# Step-down_converter.net
KiCad netlist of a schematic drawn in Altium Designer
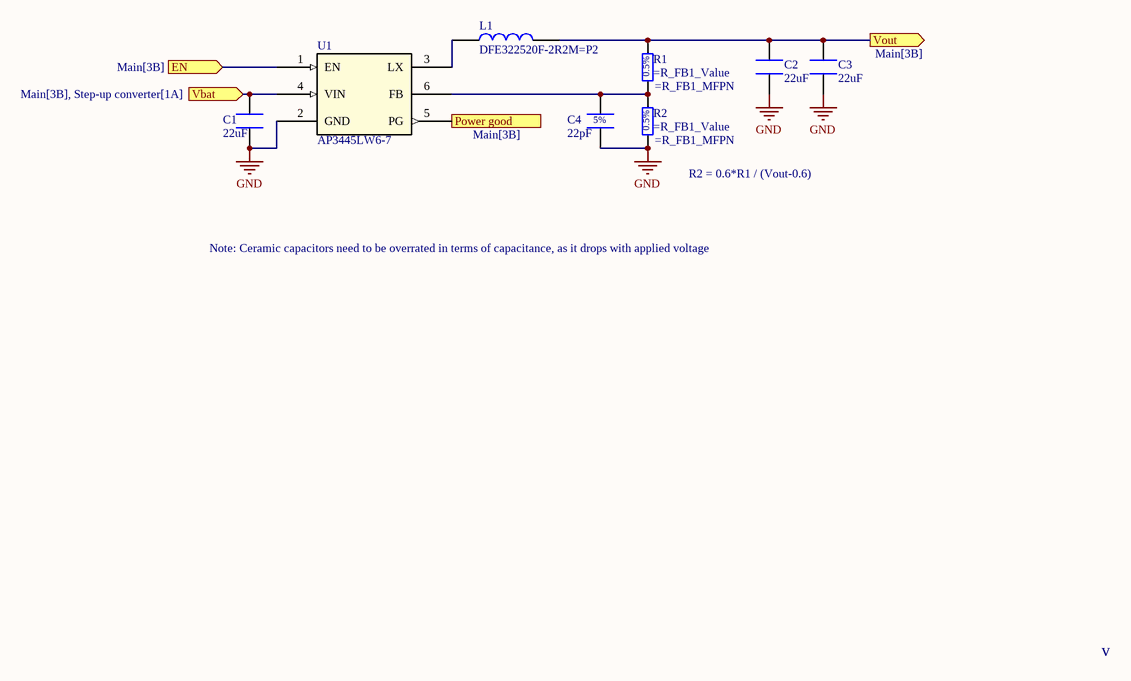
[diagram p0: Step-down converter.SchDoc]

(export (version "E")
  (design (tool "Eeschema 10.0.6"))
  (components
    (comp (ref "C1")
      (value "22uF")
      (footprint "APSS Prototype Parts:CAPACITOR_0805_2012M-70N")
      (description "Passive - Capacitor, X5R, 22uF Max, 6.3V, 0805 (2012 Metric), ±20%, -55°C ~ 85°C. 8.8uF @ 5V")
      (fields (field (name "TOLERANCE") "±20%") (field (name "MF PART NO.") "C0805C226M9PACTU"))
      (libsource (lib "APSS Prototype Parts") (part "C0805C226M9PACTU"))
    )
    (comp (ref "C2")
      (value "22uF")
      (footprint "APSS Prototype Parts:CAPACITOR_0805_2012M-70N")
      (description "Passive - Capacitor, X5R, 22uF Max, 6.3V, 0805 (2012 Metric), ±20%, -55°C ~ 85°C. 8.8uF @ 5V")
      (fields (field (name "TOLERANCE") "±20%") (field (name "MF PART NO.") "C0805C226M9PACTU"))
      (libsource (lib "APSS Prototype Parts") (part "C0805C226M9PACTU"))
    )
    (comp (ref "C3")
      (value "22uF")
      (footprint "APSS Prototype Parts:CAPACITOR_0805_2012M-70N")
      (description "Passive - Capacitor, X5R, 22uF Max, 6.3V, 0805 (2012 Metric), ±20%, -55°C ~ 85°C. 8.8uF @ 5V")
      (fields (field (name "TOLERANCE") "±20%") (field (name "MF PART NO.") "C0805C226M9PACTU"))
      (libsource (lib "APSS Prototype Parts") (part "C0805C226M9PACTU"))
    )
    (comp (ref "C4")
      (value "22pF")
      (footprint "APSS Generic Components:CAPACITOR_0805_2012M-70N")
      (description "Generic Capacitor")
      (fields (field (name "TOLERANCE") "5%") (field (name "MF PART NO.") "C0805C220J5GACTU"))
      (libsource (lib "APSS Generic Components") (part "Generic Capacitor"))
    )
    (comp (ref "L1")
      (value "DFE322520F-2R2M=P2")
      (footprint "INDC3225X200N")
      (description "2.2 H Shielded Wirewound Inductor 3.3 A 40mOhm Max 1210 (3225 Metric)")
      (libsource (lib "DFE322520F-2R2M=P2") (part "DFE322520F-2R2M=P2"))
    )
    (comp (ref "R1")
      (value "~")
      (footprint "APSS Flight Parts:Resistor_0805_2012M-50N")
      (fields
        (field (name "TOLERANCE") "0.5%")
        (field (name "POWER") "1/8W")
        (field (name "APSS STANDARD PART") "APSS Standard")
      )
      (libsource (lib "APSS Prototype Parts") (part "RG2012P-xxx-D-T5 Series"))
    )
    (comp (ref "R2")
      (value "~")
      (footprint "APSS Flight Parts:Resistor_0805_2012M-50N")
      (fields
        (field (name "TOLERANCE") "0.5%")
        (field (name "POWER") "1/8W")
        (field (name "APSS STANDARD PART") "APSS Standard")
      )
      (libsource (lib "APSS Prototype Parts") (part "RG2012P-xxx-D-T5 Series"))
    )
    (comp (ref "U1")
      (value "AP3445LW6-7")
      (footprint "APSS Prototype Parts:SOT23-5N-1.45mm")
      (description "IC - Regulator, Buck, 2A, 2.7V to 5.5V In, 0.6V to Vin Out, SOT23-6")
      (fields (field (name "APSS STANDARD PART") "APSS Standard"))
      (libsource (lib "APSS Prototype Parts") (part "AP3445LW6-7"))
    )
  )
  (nets
    (net (code "1") (name "/EN") (class "Default")
      (node (ref "U1") (pin "1") (pinfunction "EN_1") (pintype "input"))
    )
    (net (code "2") (name "/Power good") (class "Default")
      (node (ref "U1") (pin "5") (pinfunction "PG_5") (pintype "output"))
    )
    (net (code "3") (name "/Vbat") (class "Default")
      (node (ref "C1") (pin "2") (pinfunction "2_2") (pintype "passive"))
      (node (ref "U1") (pin "4") (pinfunction "VIN_4") (pintype "input"))
    )
    (net (code "4") (name "/Vout") (class "Default")
      (node (ref "C2") (pin "2") (pinfunction "2_2") (pintype "passive"))
      (node (ref "C3") (pin "2") (pinfunction "2_2") (pintype "passive"))
      (node (ref "L1") (pin "1") (pinfunction "1_1") (pintype "passive"))
      (node (ref "R1") (pin "2") (pinfunction "2_2") (pintype "passive"))
    )
    (net (code "5") (name "GND") (class "Default")
      (node (ref "C1") (pin "1") (pinfunction "1_1") (pintype "passive"))
      (node (ref "C2") (pin "1") (pinfunction "1_1") (pintype "passive"))
      (node (ref "C3") (pin "1") (pinfunction "1_1") (pintype "passive"))
      (node (ref "C4") (pin "1") (pinfunction "1_1") (pintype "passive"))
      (node (ref "R2") (pin "1") (pinfunction "1_1") (pintype "passive"))
      (node (ref "U1") (pin "2") (pinfunction "GND_2") (pintype "power_in"))
    )
    (net (code "6") (name "Net-(U1-FB)") (class "Default")
      (node (ref "C4") (pin "2") (pinfunction "2_2") (pintype "passive"))
      (node (ref "R1") (pin "1") (pinfunction "1_1") (pintype "passive"))
      (node (ref "R2") (pin "2") (pinfunction "2_2") (pintype "passive"))
      (node (ref "U1") (pin "6") (pinfunction "FB_6") (pintype "passive"))
    )
    (net (code "7") (name "Net-(U1-LX)") (class "Default")
      (node (ref "L1") (pin "2") (pinfunction "2_2") (pintype "passive"))
      (node (ref "U1") (pin "3") (pinfunction "LX_3") (pintype "passive"))
    )
  )
)
